# Eurorack_Audio_IO.net
KiCad netlist of a schematic drawn in EAGLE
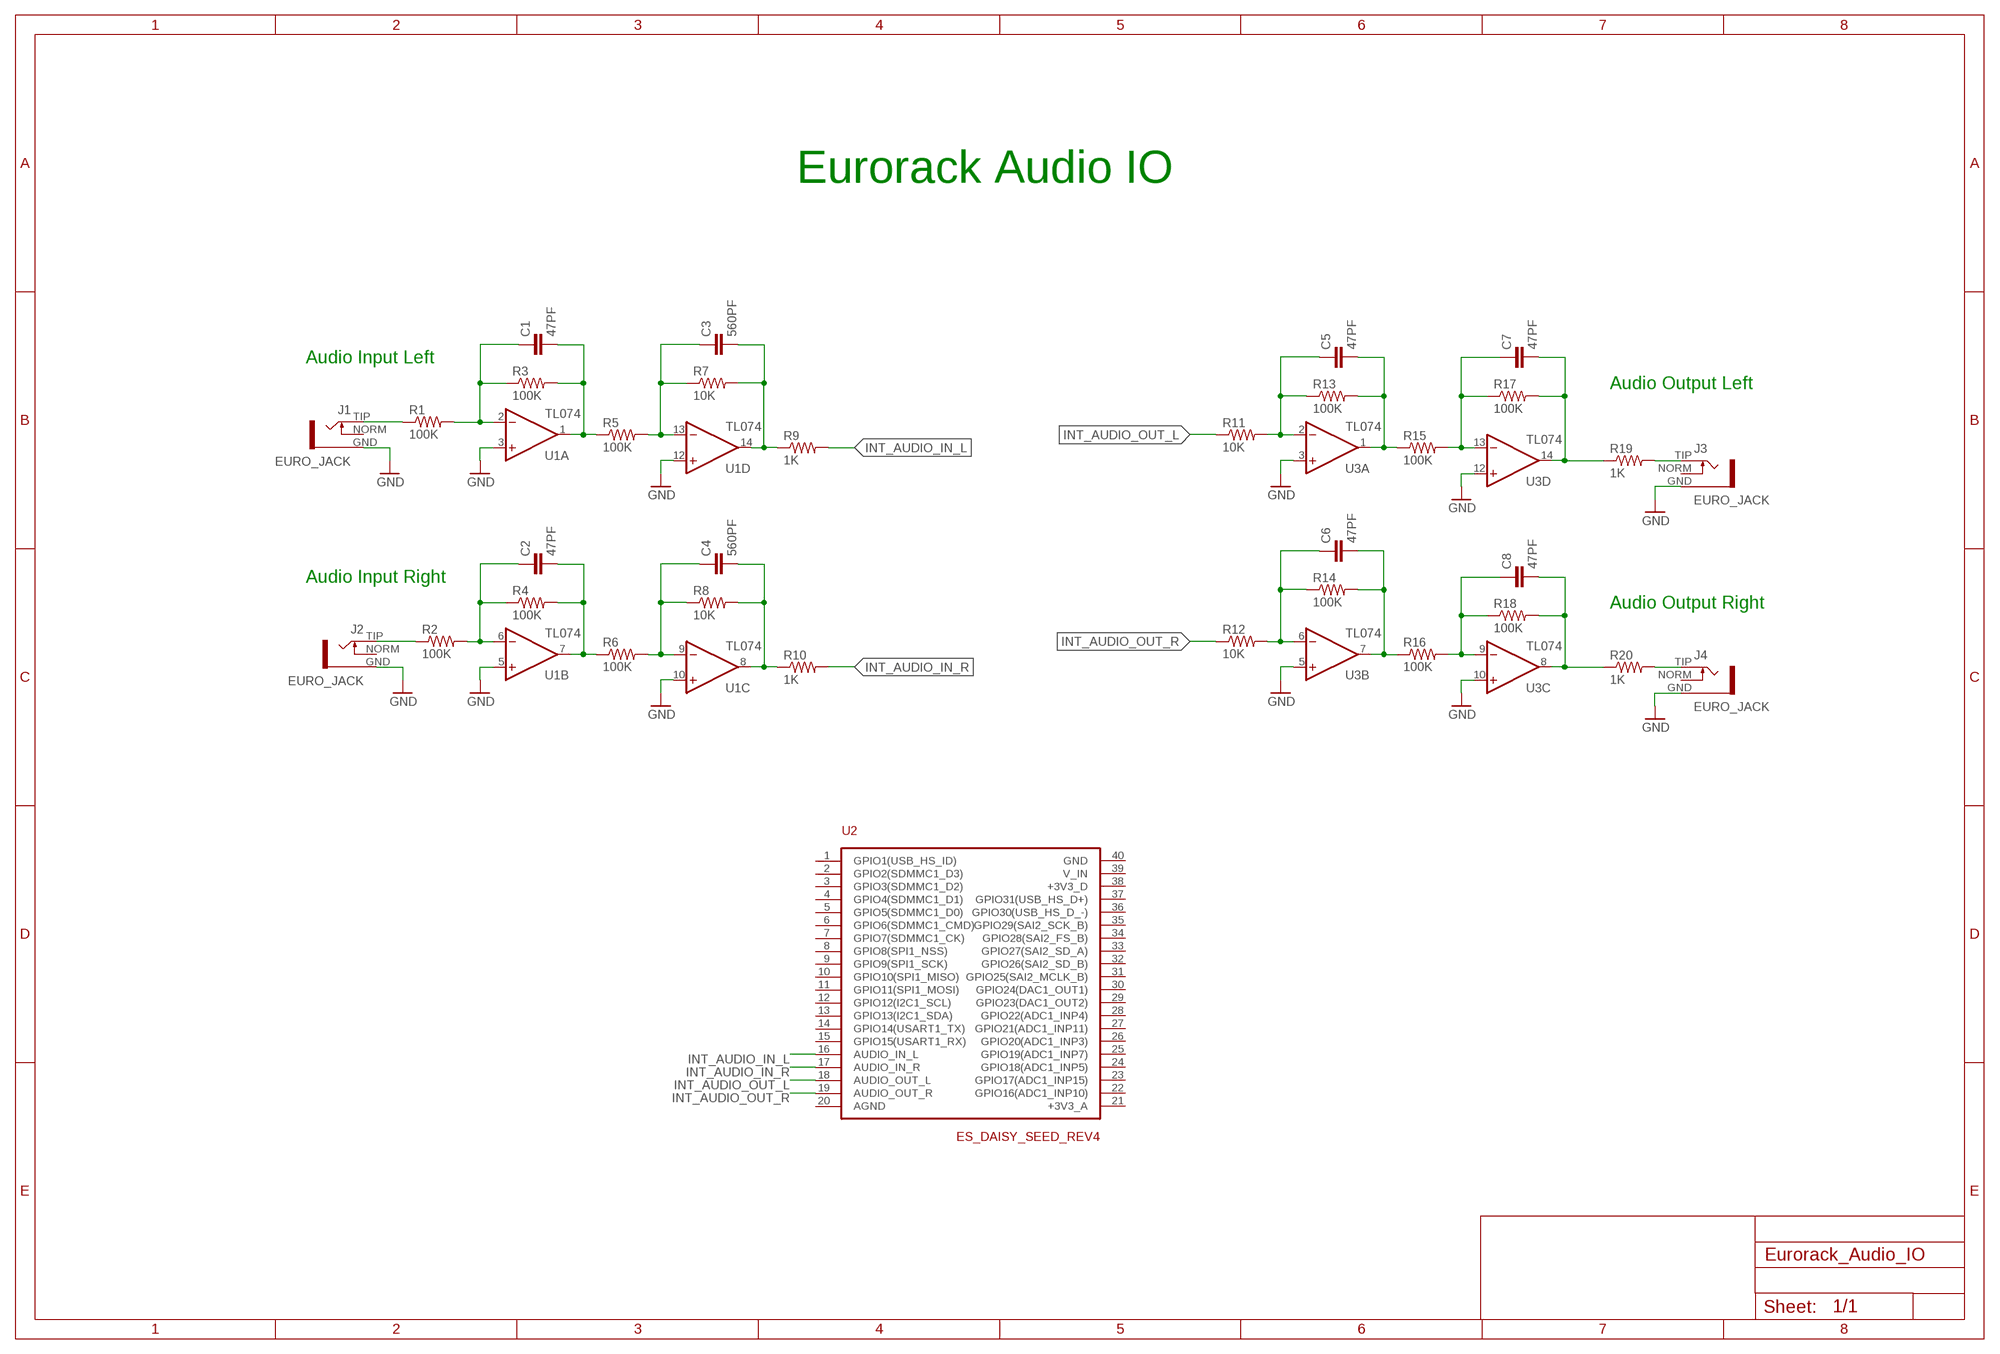
[diagram p0: schematic, sheet 1]

(export (version "E")
  (design (tool "Eeschema 10.0.6"))
  (components
    (comp (ref "C1")
      (value "47PF")
      (footprint "eagle-import:C0603")
      (libsource (lib "eagle-import") (part "C-EUC0603"))
    )
    (comp (ref "C2")
      (value "47PF")
      (footprint "eagle-import:C0603")
      (libsource (lib "eagle-import") (part "C-EUC0603"))
    )
    (comp (ref "C3")
      (value "560PF")
      (footprint "eagle-import:C0603")
      (libsource (lib "eagle-import") (part "C-EUC0603"))
    )
    (comp (ref "C4")
      (value "560PF")
      (footprint "eagle-import:C0603")
      (libsource (lib "eagle-import") (part "C-EUC0603"))
    )
    (comp (ref "C5")
      (value "47PF")
      (footprint "eagle-import:C0603")
      (libsource (lib "eagle-import") (part "C-EUC0603"))
    )
    (comp (ref "C6")
      (value "47PF")
      (footprint "eagle-import:C0603")
      (libsource (lib "eagle-import") (part "C-EUC0603"))
    )
    (comp (ref "C7")
      (value "47PF")
      (footprint "eagle-import:C0603")
      (libsource (lib "eagle-import") (part "C-EUC0603"))
    )
    (comp (ref "C8")
      (value "47PF")
      (footprint "eagle-import:C0603")
      (libsource (lib "eagle-import") (part "C-EUC0603"))
    )
    (comp (ref "J1")
      (value "EURO_JACK")
      (footprint "eagle-import:S_JACK")
      (libsource (lib "eagle-import") (part "EURO_JACK"))
    )
    (comp (ref "J2")
      (value "EURO_JACK")
      (footprint "eagle-import:S_JACK")
      (libsource (lib "eagle-import") (part "EURO_JACK"))
    )
    (comp (ref "J3")
      (value "EURO_JACK")
      (footprint "eagle-import:S_JACK")
      (libsource (lib "eagle-import") (part "EURO_JACK"))
    )
    (comp (ref "J4")
      (value "EURO_JACK")
      (footprint "eagle-import:S_JACK")
      (libsource (lib "eagle-import") (part "EURO_JACK"))
    )
    (comp (ref "R1")
      (value "100K")
      (footprint "eagle-import:R0603")
      (libsource (lib "eagle-import") (part "R-US_R0603"))
    )
    (comp (ref "R2")
      (value "100K")
      (footprint "eagle-import:R0603")
      (libsource (lib "eagle-import") (part "R-US_R0603"))
    )
    (comp (ref "R3")
      (value "100K")
      (footprint "eagle-import:R0603")
      (libsource (lib "eagle-import") (part "R-US_R0603"))
    )
    (comp (ref "R4")
      (value "100K")
      (footprint "eagle-import:R0603")
      (libsource (lib "eagle-import") (part "R-US_R0603"))
    )
    (comp (ref "R5")
      (value "100K")
      (footprint "eagle-import:R0603")
      (libsource (lib "eagle-import") (part "R-US_R0603"))
    )
    (comp (ref "R6")
      (value "100K")
      (footprint "eagle-import:R0603")
      (libsource (lib "eagle-import") (part "R-US_R0603"))
    )
    (comp (ref "R7")
      (value "10K")
      (footprint "eagle-import:R0603")
      (libsource (lib "eagle-import") (part "R-US_R0603"))
    )
    (comp (ref "R8")
      (value "10K")
      (footprint "eagle-import:R0603")
      (libsource (lib "eagle-import") (part "R-US_R0603"))
    )
    (comp (ref "R9")
      (value "1K")
      (footprint "eagle-import:R0603")
      (libsource (lib "eagle-import") (part "R-US_R0603"))
    )
    (comp (ref "R10")
      (value "1K")
      (footprint "eagle-import:R0603")
      (libsource (lib "eagle-import") (part "R-US_R0603"))
    )
    (comp (ref "R11")
      (value "10K")
      (footprint "eagle-import:R0603")
      (libsource (lib "eagle-import") (part "R-US_R0603"))
    )
    (comp (ref "R12")
      (value "10K")
      (footprint "eagle-import:R0603")
      (libsource (lib "eagle-import") (part "R-US_R0603"))
    )
    (comp (ref "R13")
      (value "100K")
      (footprint "eagle-import:R0603")
      (libsource (lib "eagle-import") (part "R-US_R0603"))
    )
    (comp (ref "R14")
      (value "100K")
      (footprint "eagle-import:R0603")
      (libsource (lib "eagle-import") (part "R-US_R0603"))
    )
    (comp (ref "R15")
      (value "100K")
      (footprint "eagle-import:R0603")
      (libsource (lib "eagle-import") (part "R-US_R0603"))
    )
    (comp (ref "R16")
      (value "100K")
      (footprint "eagle-import:R0603")
      (libsource (lib "eagle-import") (part "R-US_R0603"))
    )
    (comp (ref "R17")
      (value "100K")
      (footprint "eagle-import:R0603")
      (libsource (lib "eagle-import") (part "R-US_R0603"))
    )
    (comp (ref "R18")
      (value "100K")
      (footprint "eagle-import:R0603")
      (libsource (lib "eagle-import") (part "R-US_R0603"))
    )
    (comp (ref "R19")
      (value "1K")
      (footprint "eagle-import:R0603")
      (libsource (lib "eagle-import") (part "R-US_R0603"))
    )
    (comp (ref "R20")
      (value "1K")
      (footprint "eagle-import:R0603")
      (libsource (lib "eagle-import") (part "R-US_R0603"))
    )
    (comp (ref "U1")
      (value "TL074")
      (footprint "eagle-import:TSSOP-14")
      (fields (field (name "MPN") "TL074CPWR"))
      (libsource (lib "eagle-import") (part "TL074_TSSOP-14"))
    )
    (comp (ref "U2")
      (value "ES_DAISY_SEED_REV4")
      (footprint "eagle-import:ES_DAISY_SEED")
      (libsource (lib "eagle-import") (part "ES_DAISY_SEED_REV4"))
    )
    (comp (ref "U3")
      (value "TL074")
      (footprint "eagle-import:TSSOP-14")
      (fields (field (name "MPN") "TL074CPWR"))
      (libsource (lib "eagle-import") (part "TL074_TSSOP-14"))
    )
  )
  (nets
    (net (code "1") (name "GND") (class "Default")
      (node (ref "J1") (pin "GND") (pinfunction "GND_GND") (pintype "passive"))
      (node (ref "J2") (pin "GND") (pinfunction "GND_GND") (pintype "passive"))
      (node (ref "J3") (pin "GND") (pinfunction "GND_GND") (pintype "passive"))
      (node (ref "J4") (pin "GND") (pinfunction "GND_GND") (pintype "passive"))
      (node (ref "U1") (pin "10") (pinfunction "+IN_10") (pintype "input"))
      (node (ref "U1") (pin "12") (pinfunction "+IN_12") (pintype "input"))
      (node (ref "U1") (pin "3") (pinfunction "+IN_3") (pintype "input"))
      (node (ref "U1") (pin "5") (pinfunction "+IN_5") (pintype "input"))
      (node (ref "U3") (pin "10") (pinfunction "+IN_10") (pintype "input"))
      (node (ref "U3") (pin "12") (pinfunction "+IN_12") (pintype "input"))
      (node (ref "U3") (pin "3") (pinfunction "+IN_3") (pintype "input"))
      (node (ref "U3") (pin "5") (pinfunction "+IN_5") (pintype "input"))
    )
    (net (code "2") (name "INT_AUDIO_IN_L") (class "Default")
      (node (ref "R9") (pin "2") (pinfunction "2_2") (pintype "passive"))
      (node (ref "U2") (pin "16") (pinfunction "AUDIO_IN_L_16") (pintype "bidirectional"))
    )
    (net (code "3") (name "INT_AUDIO_IN_R") (class "Default")
      (node (ref "R10") (pin "2") (pinfunction "2_2") (pintype "passive"))
      (node (ref "U2") (pin "17") (pinfunction "AUDIO_IN_R_17") (pintype "bidirectional"))
    )
    (net (code "4") (name "INT_AUDIO_OUT_L") (class "Default")
      (node (ref "R11") (pin "1") (pinfunction "1_1") (pintype "passive"))
      (node (ref "U2") (pin "18") (pinfunction "AUDIO_OUT_L_18") (pintype "bidirectional"))
    )
    (net (code "5") (name "INT_AUDIO_OUT_R") (class "Default")
      (node (ref "R12") (pin "1") (pinfunction "1_1") (pintype "passive"))
      (node (ref "U2") (pin "19") (pinfunction "AUDIO_OUT_R_19") (pintype "bidirectional"))
    )
    (net (code "6") (name "Net-(J1-PadTIP)") (class "Default")
      (node (ref "J1") (pin "TIP") (pinfunction "TIP_TIP") (pintype "passive"))
      (node (ref "R1") (pin "1") (pinfunction "1_1") (pintype "passive"))
    )
    (net (code "7") (name "Net-(J2-PadTIP)") (class "Default")
      (node (ref "J2") (pin "TIP") (pinfunction "TIP_TIP") (pintype "passive"))
      (node (ref "R2") (pin "1") (pinfunction "1_1") (pintype "passive"))
    )
    (net (code "8") (name "Net-(J3-PadTIP)") (class "Default")
      (node (ref "J3") (pin "TIP") (pinfunction "TIP_TIP") (pintype "passive"))
      (node (ref "R19") (pin "2") (pinfunction "2_2") (pintype "passive"))
    )
    (net (code "9") (name "Net-(J4-PadTIP)") (class "Default")
      (node (ref "J4") (pin "TIP") (pinfunction "TIP_TIP") (pintype "passive"))
      (node (ref "R20") (pin "2") (pinfunction "2_2") (pintype "passive"))
    )
    (net (code "10") (name "Net-(U1A--IN)") (class "Default")
      (node (ref "C1") (pin "1") (pinfunction "1_1") (pintype "passive"))
      (node (ref "R1") (pin "2") (pinfunction "2_2") (pintype "passive"))
      (node (ref "R3") (pin "1") (pinfunction "1_1") (pintype "passive"))
      (node (ref "U1") (pin "2") (pinfunction "-IN_2") (pintype "input"))
    )
    (net (code "11") (name "Net-(U1A-OUT)") (class "Default")
      (node (ref "C1") (pin "2") (pinfunction "2_2") (pintype "passive"))
      (node (ref "R3") (pin "2") (pinfunction "2_2") (pintype "passive"))
      (node (ref "R5") (pin "1") (pinfunction "1_1") (pintype "passive"))
      (node (ref "U1") (pin "1") (pinfunction "OUT_1") (pintype "output"))
    )
    (net (code "12") (name "Net-(U1B--IN)") (class "Default")
      (node (ref "C2") (pin "1") (pinfunction "1_1") (pintype "passive"))
      (node (ref "R2") (pin "2") (pinfunction "2_2") (pintype "passive"))
      (node (ref "R4") (pin "1") (pinfunction "1_1") (pintype "passive"))
      (node (ref "U1") (pin "6") (pinfunction "-IN_6") (pintype "input"))
    )
    (net (code "13") (name "Net-(U1B-OUT)") (class "Default")
      (node (ref "C2") (pin "2") (pinfunction "2_2") (pintype "passive"))
      (node (ref "R4") (pin "2") (pinfunction "2_2") (pintype "passive"))
      (node (ref "R6") (pin "1") (pinfunction "1_1") (pintype "passive"))
      (node (ref "U1") (pin "7") (pinfunction "OUT_7") (pintype "output"))
    )
    (net (code "14") (name "Net-(U1C--IN)") (class "Default")
      (node (ref "C4") (pin "1") (pinfunction "1_1") (pintype "passive"))
      (node (ref "R6") (pin "2") (pinfunction "2_2") (pintype "passive"))
      (node (ref "R8") (pin "1") (pinfunction "1_1") (pintype "passive"))
      (node (ref "U1") (pin "9") (pinfunction "-IN_9") (pintype "input"))
    )
    (net (code "15") (name "Net-(U1C-OUT)") (class "Default")
      (node (ref "C4") (pin "2") (pinfunction "2_2") (pintype "passive"))
      (node (ref "R10") (pin "1") (pinfunction "1_1") (pintype "passive"))
      (node (ref "R8") (pin "2") (pinfunction "2_2") (pintype "passive"))
      (node (ref "U1") (pin "8") (pinfunction "OUT_8") (pintype "output"))
    )
    (net (code "16") (name "Net-(U1D--IN)") (class "Default")
      (node (ref "C3") (pin "1") (pinfunction "1_1") (pintype "passive"))
      (node (ref "R5") (pin "2") (pinfunction "2_2") (pintype "passive"))
      (node (ref "R7") (pin "1") (pinfunction "1_1") (pintype "passive"))
      (node (ref "U1") (pin "13") (pinfunction "-IN_13") (pintype "input"))
    )
    (net (code "17") (name "Net-(U1D-OUT)") (class "Default")
      (node (ref "C3") (pin "2") (pinfunction "2_2") (pintype "passive"))
      (node (ref "R7") (pin "2") (pinfunction "2_2") (pintype "passive"))
      (node (ref "R9") (pin "1") (pinfunction "1_1") (pintype "passive"))
      (node (ref "U1") (pin "14") (pinfunction "OUT_14") (pintype "output"))
    )
    (net (code "18") (name "Net-(U3A--IN)") (class "Default")
      (node (ref "C5") (pin "1") (pinfunction "1_1") (pintype "passive"))
      (node (ref "R11") (pin "2") (pinfunction "2_2") (pintype "passive"))
      (node (ref "R13") (pin "1") (pinfunction "1_1") (pintype "passive"))
      (node (ref "U3") (pin "2") (pinfunction "-IN_2") (pintype "input"))
    )
    (net (code "19") (name "Net-(U3A-OUT)") (class "Default")
      (node (ref "C5") (pin "2") (pinfunction "2_2") (pintype "passive"))
      (node (ref "R13") (pin "2") (pinfunction "2_2") (pintype "passive"))
      (node (ref "R15") (pin "1") (pinfunction "1_1") (pintype "passive"))
      (node (ref "U3") (pin "1") (pinfunction "OUT_1") (pintype "output"))
    )
    (net (code "20") (name "Net-(U3B--IN)") (class "Default")
      (node (ref "C6") (pin "1") (pinfunction "1_1") (pintype "passive"))
      (node (ref "R12") (pin "2") (pinfunction "2_2") (pintype "passive"))
      (node (ref "R14") (pin "1") (pinfunction "1_1") (pintype "passive"))
      (node (ref "U3") (pin "6") (pinfunction "-IN_6") (pintype "input"))
    )
    (net (code "21") (name "Net-(U3B-OUT)") (class "Default")
      (node (ref "C6") (pin "2") (pinfunction "2_2") (pintype "passive"))
      (node (ref "R14") (pin "2") (pinfunction "2_2") (pintype "passive"))
      (node (ref "R16") (pin "1") (pinfunction "1_1") (pintype "passive"))
      (node (ref "U3") (pin "7") (pinfunction "OUT_7") (pintype "output"))
    )
    (net (code "22") (name "Net-(U3C--IN)") (class "Default")
      (node (ref "C8") (pin "1") (pinfunction "1_1") (pintype "passive"))
      (node (ref "R16") (pin "2") (pinfunction "2_2") (pintype "passive"))
      (node (ref "R18") (pin "1") (pinfunction "1_1") (pintype "passive"))
      (node (ref "U3") (pin "9") (pinfunction "-IN_9") (pintype "input"))
    )
    (net (code "23") (name "Net-(U3C-OUT)") (class "Default")
      (node (ref "C8") (pin "2") (pinfunction "2_2") (pintype "passive"))
      (node (ref "R18") (pin "2") (pinfunction "2_2") (pintype "passive"))
      (node (ref "R20") (pin "1") (pinfunction "1_1") (pintype "passive"))
      (node (ref "U3") (pin "8") (pinfunction "OUT_8") (pintype "output"))
    )
    (net (code "24") (name "Net-(U3D--IN)") (class "Default")
      (node (ref "C7") (pin "1") (pinfunction "1_1") (pintype "passive"))
      (node (ref "R15") (pin "2") (pinfunction "2_2") (pintype "passive"))
      (node (ref "R17") (pin "1") (pinfunction "1_1") (pintype "passive"))
      (node (ref "U3") (pin "13") (pinfunction "-IN_13") (pintype "input"))
    )
    (net (code "25") (name "Net-(U3D-OUT)") (class "Default")
      (node (ref "C7") (pin "2") (pinfunction "2_2") (pintype "passive"))
      (node (ref "R17") (pin "2") (pinfunction "2_2") (pintype "passive"))
      (node (ref "R19") (pin "1") (pinfunction "1_1") (pintype "passive"))
      (node (ref "U3") (pin "14") (pinfunction "OUT_14") (pintype "output"))
    )
    (net (code "26") (name "unconnected-(J1-PadNORM)") (class "Default")
      (node (ref "J1") (pin "NORM") (pinfunction "NORM_NORM") (pintype "passive"))
    )
    (net (code "27") (name "unconnected-(J2-PadNORM)") (class "Default")
      (node (ref "J2") (pin "NORM") (pinfunction "NORM_NORM") (pintype "passive"))
    )
    (net (code "28") (name "unconnected-(J3-PadNORM)") (class "Default")
      (node (ref "J3") (pin "NORM") (pinfunction "NORM_NORM") (pintype "passive"))
    )
    (net (code "29") (name "unconnected-(J4-PadNORM)") (class "Default")
      (node (ref "J4") (pin "NORM") (pinfunction "NORM_NORM") (pintype "passive"))
    )
    (net (code "30") (name "unconnected-(U2-+3V3_A-Pad21)") (class "Default")
      (node (ref "U2") (pin "21") (pinfunction "+3V3_A_21") (pintype "bidirectional"))
    )
    (net (code "31") (name "unconnected-(U2-+3V3_D-Pad38)") (class "Default")
      (node (ref "U2") (pin "38") (pinfunction "+3V3_D_38") (pintype "bidirectional"))
    )
    (net (code "32") (name "unconnected-(U2-AGND-Pad20)") (class "Default")
      (node (ref "U2") (pin "20") (pinfunction "AGND_20") (pintype "bidirectional"))
    )
    (net (code "33") (name "unconnected-(U2-GND-Pad40)") (class "Default")
      (node (ref "U2") (pin "40") (pinfunction "GND_40") (pintype "bidirectional"))
    )
    (net (code "34") (name "unconnected-(U2-GPIO1(USB_HS_ID)-Pad1)") (class "Default")
      (node (ref "U2") (pin "1") (pinfunction "GPIO1(USB_HS_ID)_1") (pintype "bidirectional"))
    )
    (net (code "35") (name "unconnected-(U2-GPIO2(SDMMC1_D3)-Pad2)") (class "Default")
      (node (ref "U2") (pin "2") (pinfunction "GPIO2(SDMMC1_D3)_2") (pintype "bidirectional"))
    )
    (net (code "36") (name "unconnected-(U2-GPIO3(SDMMC1_D2)-Pad3)") (class "Default")
      (node (ref "U2") (pin "3") (pinfunction "GPIO3(SDMMC1_D2)_3") (pintype "bidirectional"))
    )
    (net (code "37") (name "unconnected-(U2-GPIO4(SDMMC1_D1)-Pad4)") (class "Default")
      (node (ref "U2") (pin "4") (pinfunction "GPIO4(SDMMC1_D1)_4") (pintype "bidirectional"))
    )
    (net (code "38") (name "unconnected-(U2-GPIO5(SDMMC1_D0)-Pad5)") (class "Default")
      (node (ref "U2") (pin "5") (pinfunction "GPIO5(SDMMC1_D0)_5") (pintype "bidirectional"))
    )
    (net (code "39") (name "unconnected-(U2-GPIO6(SDMMC1_CMD)-Pad6)") (class "Default")
      (node (ref "U2") (pin "6") (pinfunction "GPIO6(SDMMC1_CMD)_6") (pintype "bidirectional"))
    )
    (net (code "40") (name "unconnected-(U2-GPIO7(SDMMC1_CK)-Pad7)") (class "Default")
      (node (ref "U2") (pin "7") (pinfunction "GPIO7(SDMMC1_CK)_7") (pintype "bidirectional"))
    )
    (net (code "41") (name "unconnected-(U2-GPIO8(SPI1_NSS)-Pad8)") (class "Default")
      (node (ref "U2") (pin "8") (pinfunction "GPIO8(SPI1_NSS)_8") (pintype "bidirectional"))
    )
    (net (code "42") (name "unconnected-(U2-GPIO9(SPI1_SCK)-Pad9)") (class "Default")
      (node (ref "U2") (pin "9") (pinfunction "GPIO9(SPI1_SCK)_9") (pintype "bidirectional"))
    )
    (net (code "43") (name "unconnected-(U2-GPIO10(SPI1_MISO)-Pad10)") (class "Default")
      (node (ref "U2") (pin "10") (pinfunction "GPIO10(SPI1_MISO)_10") (pintype "bidirectional"))
    )
    (net (code "44") (name "unconnected-(U2-GPIO11(SPI1_MOSI)-Pad11)") (class "Default")
      (node (ref "U2") (pin "11") (pinfunction "GPIO11(SPI1_MOSI)_11") (pintype "bidirectional"))
    )
    (net (code "45") (name "unconnected-(U2-GPIO12(I2C1_SCL)-Pad12)") (class "Default")
      (node (ref "U2") (pin "12") (pinfunction "GPIO12(I2C1_SCL)_12") (pintype "bidirectional"))
    )
    (net (code "46") (name "unconnected-(U2-GPIO13(I2C1_SDA)-Pad13)") (class "Default")
      (node (ref "U2") (pin "13") (pinfunction "GPIO13(I2C1_SDA)_13") (pintype "bidirectional"))
    )
    (net (code "47") (name "unconnected-(U2-GPIO14(USART1_TX)-Pad14)") (class "Default")
      (node (ref "U2") (pin "14") (pinfunction "GPIO14(USART1_TX)_14") (pintype "bidirectional"))
    )
    (net (code "48") (name "unconnected-(U2-GPIO15(USART1_RX)-Pad15)") (class "Default")
      (node (ref "U2") (pin "15") (pinfunction "GPIO15(USART1_RX)_15") (pintype "bidirectional"))
    )
    (net (code "49") (name "unconnected-(U2-GPIO16(ADC1_INP10)-Pad22)") (class "Default")
      (node (ref "U2") (pin "22") (pinfunction "GPIO16(ADC1_INP10)_22") (pintype "bidirectional"))
    )
    (net (code "50") (name "unconnected-(U2-GPIO17(ADC1_INP15)-Pad23)") (class "Default")
      (node (ref "U2") (pin "23") (pinfunction "GPIO17(ADC1_INP15)_23") (pintype "bidirectional"))
    )
    (net (code "51") (name "unconnected-(U2-GPIO18(ADC1_INP5)-Pad24)") (class "Default")
      (node (ref "U2") (pin "24") (pinfunction "GPIO18(ADC1_INP5)_24") (pintype "bidirectional"))
    )
    (net (code "52") (name "unconnected-(U2-GPIO19(ADC1_INP7)-Pad25)") (class "Default")
      (node (ref "U2") (pin "25") (pinfunction "GPIO19(ADC1_INP7)_25") (pintype "bidirectional"))
    )
    (net (code "53") (name "unconnected-(U2-GPIO20(ADC1_INP3)-Pad26)") (class "Default")
      (node (ref "U2") (pin "26") (pinfunction "GPIO20(ADC1_INP3)_26") (pintype "bidirectional"))
    )
    (net (code "54") (name "unconnected-(U2-GPIO21(ADC1_INP11)-Pad27)") (class "Default")
      (node (ref "U2") (pin "27") (pinfunction "GPIO21(ADC1_INP11)_27") (pintype "bidirectional"))
    )
    (net (code "55") (name "unconnected-(U2-GPIO22(ADC1_INP4)-Pad28)") (class "Default")
      (node (ref "U2") (pin "28") (pinfunction "GPIO22(ADC1_INP4)_28") (pintype "bidirectional"))
    )
    (net (code "56") (name "unconnected-(U2-GPIO23(DAC1_OUT2)-Pad29)") (class "Default")
      (node (ref "U2") (pin "29") (pinfunction "GPIO23(DAC1_OUT2)_29") (pintype "bidirectional"))
    )
    (net (code "57") (name "unconnected-(U2-GPIO24(DAC1_OUT1)-Pad30)") (class "Default")
      (node (ref "U2") (pin "30") (pinfunction "GPIO24(DAC1_OUT1)_30") (pintype "bidirectional"))
    )
    (net (code "58") (name "unconnected-(U2-GPIO25(SAI2_MCLK_B)-Pad31)") (class "Default")
      (node (ref "U2") (pin "31") (pinfunction "GPIO25(SAI2_MCLK_B)_31") (pintype "bidirectional"))
    )
    (net (code "59") (name "unconnected-(U2-GPIO26(SAI2_SD_B)-Pad32)") (class "Default")
      (node (ref "U2") (pin "32") (pinfunction "GPIO26(SAI2_SD_B)_32") (pintype "bidirectional"))
    )
    (net (code "60") (name "unconnected-(U2-GPIO27(SAI2_SD_A)-Pad33)") (class "Default")
      (node (ref "U2") (pin "33") (pinfunction "GPIO27(SAI2_SD_A)_33") (pintype "bidirectional"))
    )
    (net (code "61") (name "unconnected-(U2-GPIO28(SAI2_FS_B)-Pad34)") (class "Default")
      (node (ref "U2") (pin "34") (pinfunction "GPIO28(SAI2_FS_B)_34") (pintype "bidirectional"))
    )
    (net (code "62") (name "unconnected-(U2-GPIO29(SAI2_SCK_B)-Pad35)") (class "Default")
      (node (ref "U2") (pin "35") (pinfunction "GPIO29(SAI2_SCK_B)_35") (pintype "bidirectional"))
    )
    (net (code "63") (name "unconnected-(U2-GPIO30(USB_HS_D_-)-Pad36)") (class "Default")
      (node (ref "U2") (pin "36") (pinfunction "GPIO30(USB_HS_D_-)_36") (pintype "bidirectional"))
    )
    (net (code "64") (name "unconnected-(U2-GPIO31(USB_HS_D+)-Pad37)") (class "Default")
      (node (ref "U2") (pin "37") (pinfunction "GPIO31(USB_HS_D+)_37") (pintype "bidirectional"))
    )
    (net (code "65") (name "unconnected-(U2-V_IN-Pad39)") (class "Default")
      (node (ref "U2") (pin "39") (pinfunction "V_IN_39") (pintype "bidirectional"))
    )
  )
)
